# rPiMIDIShield.net
KiCad netlist of a schematic drawn in EAGLE
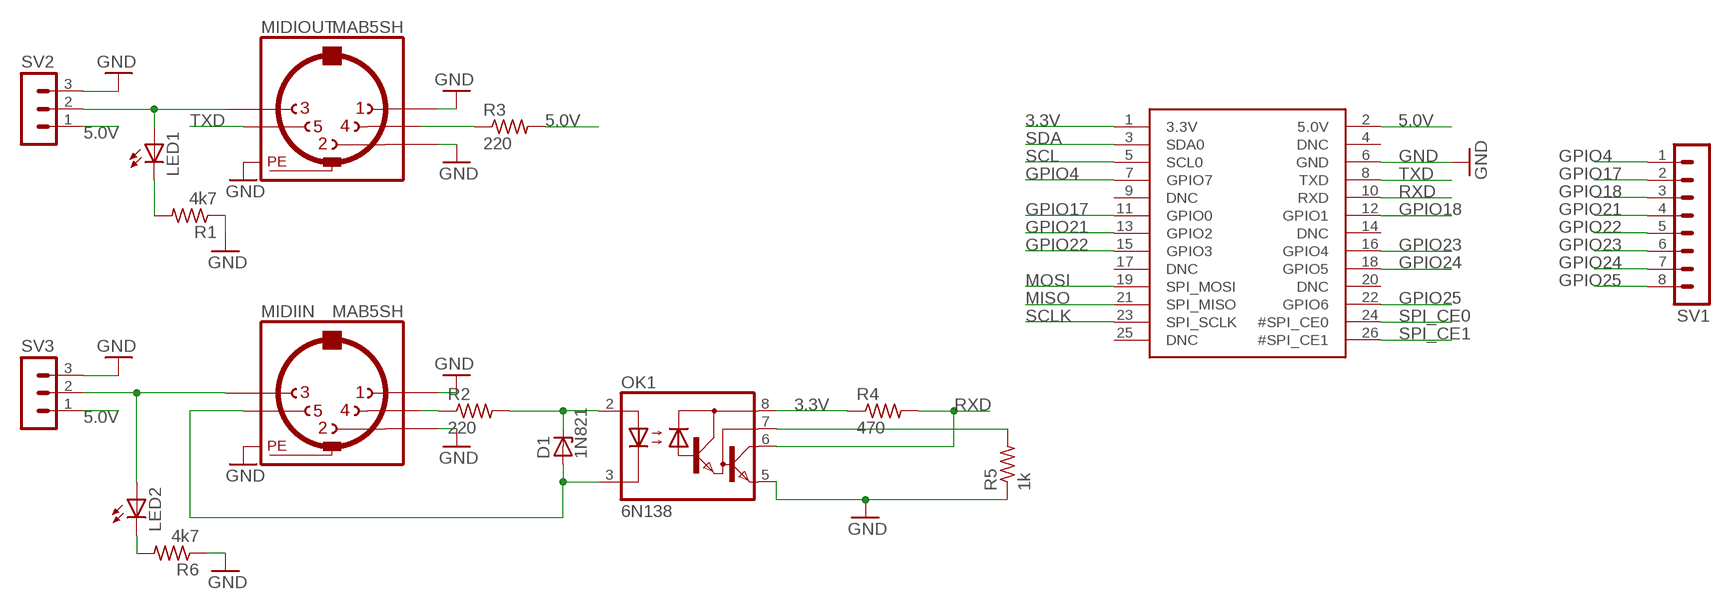
[diagram p0: schematic, sheet 1]

(export (version "E")
  (design (tool "Eeschema 10.0.6"))
  (components
    (comp (ref "D1")
      (value "1N821")
      (footprint "eagle-import:DO35Z10")
      (libsource (lib "eagle-import") (part "1N821"))
    )
    (comp (ref "GPIO")
      (value "RASPBERRYPI_BB")
      (footprint "eagle-import:RASBERRYPI_SHIELD")
      (libsource (lib "eagle-import") (part "RASPBERRYPI_BB"))
    )
    (comp (ref "LED1")
      (value "LEDLSU260")
      (footprint "eagle-import:LSU260")
      (libsource (lib "eagle-import") (part "LEDLSU260"))
    )
    (comp (ref "LED2")
      (value "LEDLSU260")
      (footprint "eagle-import:LSU260")
      (libsource (lib "eagle-import") (part "LEDLSU260"))
    )
    (comp (ref "MIDIIN")
      (value "MAB5SH")
      (footprint "eagle-import:MAB5SH")
      (libsource (lib "eagle-import") (part "MAB5SH"))
    )
    (comp (ref "MIDIOUT")
      (value "MAB5SH")
      (footprint "eagle-import:MAB5SH")
      (libsource (lib "eagle-import") (part "MAB5SH"))
    )
    (comp (ref "OK1")
      (value "6N138")
      (footprint "eagle-import:DIL08")
      (fields (field (name "MF") "VISHAY/TELEFUNKEN"))
      (libsource (lib "eagle-import") (part "6N138"))
    )
    (comp (ref "R1")
      (value "4k7")
      (footprint "eagle-import:0204_7")
      (libsource (lib "eagle-import") (part "R-US_0204/7"))
    )
    (comp (ref "R2")
      (value "220")
      (footprint "eagle-import:0204_7")
      (libsource (lib "eagle-import") (part "R-US_0204/7"))
    )
    (comp (ref "R3")
      (value "220")
      (footprint "eagle-import:0204_7")
      (libsource (lib "eagle-import") (part "R-US_0204/7"))
    )
    (comp (ref "R4")
      (value "470")
      (footprint "eagle-import:0204_7")
      (libsource (lib "eagle-import") (part "R-US_0204/7"))
    )
    (comp (ref "R5")
      (value "1k")
      (footprint "eagle-import:0204_7")
      (libsource (lib "eagle-import") (part "R-US_0204/7"))
    )
    (comp (ref "R6")
      (value "4k7")
      (footprint "eagle-import:0204_7")
      (libsource (lib "eagle-import") (part "R-US_0204/7"))
    )
    (comp (ref "SV1")
      (value "MA08-1")
      (footprint "eagle-import:MA08-1")
      (libsource (lib "eagle-import") (part "MA08-1"))
    )
    (comp (ref "SV2")
      (value "MA03-1")
      (footprint "eagle-import:MA03-1")
      (libsource (lib "eagle-import") (part "MA03-1"))
    )
    (comp (ref "SV3")
      (value "MA03-1")
      (footprint "eagle-import:MA03-1")
      (libsource (lib "eagle-import") (part "MA03-1"))
    )
  )
  (nets
    (net (code "1") (name "/3.3V") (class "Default")
      (node (ref "GPIO") (pin "1") (pinfunction "3.3V_1") (pintype "power_in"))
      (node (ref "OK1") (pin "8") (pinfunction "VCC_8") (pintype "passive"))
      (node (ref "R4") (pin "1") (pinfunction "1_1") (pintype "passive"))
    )
    (net (code "2") (name "/5.0V") (class "Default")
      (node (ref "GPIO") (pin "2") (pinfunction "5.0V_2") (pintype "power_in"))
      (node (ref "R3") (pin "2") (pinfunction "2_2") (pintype "passive"))
      (node (ref "SV2") (pin "1") (pinfunction "1_1") (pintype "passive"))
      (node (ref "SV3") (pin "1") (pinfunction "1_1") (pintype "passive"))
    )
    (net (code "3") (name "/GPIO4") (class "Default")
      (node (ref "GPIO") (pin "7") (pinfunction "GPIO7_7") (pintype "bidirectional"))
      (node (ref "SV1") (pin "1") (pinfunction "1_1") (pintype "passive"))
    )
    (net (code "4") (name "/GPIO17") (class "Default")
      (node (ref "GPIO") (pin "11") (pinfunction "GPIO0_11") (pintype "bidirectional"))
      (node (ref "SV1") (pin "2") (pinfunction "2_2") (pintype "passive"))
    )
    (net (code "5") (name "/GPIO18") (class "Default")
      (node (ref "GPIO") (pin "12") (pinfunction "GPIO1_12") (pintype "bidirectional"))
      (node (ref "SV1") (pin "3") (pinfunction "3_3") (pintype "passive"))
    )
    (net (code "6") (name "/GPIO21") (class "Default")
      (node (ref "GPIO") (pin "13") (pinfunction "GPIO2_13") (pintype "bidirectional"))
      (node (ref "SV1") (pin "4") (pinfunction "4_4") (pintype "passive"))
    )
    (net (code "7") (name "/GPIO22") (class "Default")
      (node (ref "GPIO") (pin "15") (pinfunction "GPIO3_15") (pintype "bidirectional"))
      (node (ref "SV1") (pin "5") (pinfunction "5_5") (pintype "passive"))
    )
    (net (code "8") (name "/GPIO23") (class "Default")
      (node (ref "GPIO") (pin "16") (pinfunction "GPIO4_16") (pintype "bidirectional"))
      (node (ref "SV1") (pin "6") (pinfunction "6_6") (pintype "passive"))
    )
    (net (code "9") (name "/GPIO24") (class "Default")
      (node (ref "GPIO") (pin "18") (pinfunction "GPIO5_18") (pintype "bidirectional"))
      (node (ref "SV1") (pin "7") (pinfunction "7_7") (pintype "passive"))
    )
    (net (code "10") (name "/GPIO25") (class "Default")
      (node (ref "GPIO") (pin "22") (pinfunction "GPIO6_22") (pintype "bidirectional"))
      (node (ref "SV1") (pin "8") (pinfunction "8_8") (pintype "passive"))
    )
    (net (code "11") (name "/MISO") (class "Default")
      (node (ref "GPIO") (pin "21") (pinfunction "SPI_MISO_21") (pintype "input"))
    )
    (net (code "12") (name "/MOSI") (class "Default")
      (node (ref "GPIO") (pin "19") (pinfunction "SPI_MOSI_19") (pintype "output"))
    )
    (net (code "13") (name "/RXD") (class "Default")
      (node (ref "GPIO") (pin "10") (pinfunction "RXD_10") (pintype "input"))
      (node (ref "OK1") (pin "6") (pinfunction "VO_6") (pintype "passive"))
      (node (ref "R4") (pin "2") (pinfunction "2_2") (pintype "passive"))
    )
    (net (code "14") (name "/SCL") (class "Default")
      (node (ref "GPIO") (pin "5") (pinfunction "SCL0_5") (pintype "output"))
    )
    (net (code "15") (name "/SCLK") (class "Default")
      (node (ref "GPIO") (pin "23") (pinfunction "SPI_SCLK_23") (pintype "output"))
    )
    (net (code "16") (name "/SDA") (class "Default")
      (node (ref "GPIO") (pin "3") (pinfunction "SDA0_3") (pintype "bidirectional"))
    )
    (net (code "17") (name "/SPI_CE0") (class "Default")
      (node (ref "GPIO") (pin "24") (pinfunction "#SPI_CE0_24") (pintype "output"))
    )
    (net (code "18") (name "/SPI_CE1") (class "Default")
      (node (ref "GPIO") (pin "26") (pinfunction "#SPI_CE1_26") (pintype "output"))
    )
    (net (code "19") (name "/TXD") (class "Default")
      (node (ref "GPIO") (pin "8") (pinfunction "TXD_8") (pintype "output"))
      (node (ref "MIDIOUT") (pin "5") (pinfunction "5_5") (pintype "passive"))
    )
    (net (code "20") (name "GND") (class "Default")
      (node (ref "GPIO") (pin "6") (pinfunction "GND_6") (pintype "power_in"))
      (node (ref "MIDIIN") (pin "1") (pinfunction "1_1") (pintype "passive"))
      (node (ref "MIDIIN") (pin "2") (pinfunction "2_2") (pintype "passive"))
      (node (ref "MIDIIN") (pin "PE") (pinfunction "PE_PE") (pintype "power_in"))
      (node (ref "MIDIIN") (pin "PE@") (pinfunction "PE_PE@") (pintype "power_in"))
      (node (ref "MIDIOUT") (pin "1") (pinfunction "1_1") (pintype "passive"))
      (node (ref "MIDIOUT") (pin "2") (pinfunction "2_2") (pintype "passive"))
      (node (ref "MIDIOUT") (pin "PE") (pinfunction "PE_PE") (pintype "power_in"))
      (node (ref "MIDIOUT") (pin "PE@") (pinfunction "PE_PE@") (pintype "power_in"))
      (node (ref "OK1") (pin "5") (pinfunction "GND_5") (pintype "passive"))
      (node (ref "R1") (pin "1") (pinfunction "1_1") (pintype "passive"))
      (node (ref "R5") (pin "1") (pinfunction "1_1") (pintype "passive"))
      (node (ref "R6") (pin "1") (pinfunction "1_1") (pintype "passive"))
      (node (ref "SV2") (pin "3") (pinfunction "3_3") (pintype "passive"))
      (node (ref "SV3") (pin "3") (pinfunction "3_3") (pintype "passive"))
    )
    (net (code "21") (name "Net-(LED1-C)") (class "Default")
      (node (ref "LED1") (pin "K") (pinfunction "C_K") (pintype "passive"))
      (node (ref "R1") (pin "2") (pinfunction "2_2") (pintype "passive"))
    )
    (net (code "22") (name "Net-(LED1-PadA)") (class "Default")
      (node (ref "LED1") (pin "A") (pinfunction "A_A") (pintype "passive"))
      (node (ref "MIDIOUT") (pin "3") (pinfunction "3_3") (pintype "passive"))
      (node (ref "SV2") (pin "2") (pinfunction "2_2") (pintype "passive"))
    )
    (net (code "23") (name "Net-(LED2-C)") (class "Default")
      (node (ref "LED2") (pin "K") (pinfunction "C_K") (pintype "passive"))
      (node (ref "R6") (pin "2") (pinfunction "2_2") (pintype "passive"))
    )
    (net (code "24") (name "Net-(LED2-PadA)") (class "Default")
      (node (ref "LED2") (pin "A") (pinfunction "A_A") (pintype "passive"))
      (node (ref "MIDIIN") (pin "3") (pinfunction "3_3") (pintype "passive"))
      (node (ref "SV3") (pin "2") (pinfunction "2_2") (pintype "passive"))
    )
    (net (code "25") (name "Net-(MIDIIN-Pad4)") (class "Default")
      (node (ref "MIDIIN") (pin "4") (pinfunction "4_4") (pintype "passive"))
      (node (ref "R2") (pin "1") (pinfunction "1_1") (pintype "passive"))
    )
    (net (code "26") (name "Net-(MIDIOUT-Pad4)") (class "Default")
      (node (ref "MIDIOUT") (pin "4") (pinfunction "4_4") (pintype "passive"))
      (node (ref "R3") (pin "1") (pinfunction "1_1") (pintype "passive"))
    )
    (net (code "27") (name "Net-(OK1-A)") (class "Default")
      (node (ref "D1") (pin "C") (pinfunction "C_C") (pintype "passive"))
      (node (ref "OK1") (pin "2") (pinfunction "A_2") (pintype "passive"))
      (node (ref "R2") (pin "2") (pinfunction "2_2") (pintype "passive"))
    )
    (net (code "28") (name "Net-(OK1-C)") (class "Default")
      (node (ref "D1") (pin "A") (pinfunction "A_A") (pintype "passive"))
      (node (ref "MIDIIN") (pin "5") (pinfunction "5_5") (pintype "passive"))
      (node (ref "OK1") (pin "3") (pinfunction "C_3") (pintype "passive"))
    )
    (net (code "29") (name "Net-(OK1-VB)") (class "Default")
      (node (ref "OK1") (pin "7") (pinfunction "VB_7") (pintype "passive"))
      (node (ref "R5") (pin "2") (pinfunction "2_2") (pintype "passive"))
    )
    (net (code "30") (name "unconnected-(GPIO-DNC-Pad4)") (class "Default")
      (node (ref "GPIO") (pin "4") (pinfunction "DNC_4") (pintype "no_connect"))
    )
    (net (code "31") (name "unconnected-(GPIO-DNC-Pad9)") (class "Default")
      (node (ref "GPIO") (pin "9") (pinfunction "DNC_9") (pintype "no_connect"))
    )
    (net (code "32") (name "unconnected-(GPIO-DNC-Pad14)") (class "Default")
      (node (ref "GPIO") (pin "14") (pinfunction "DNC_14") (pintype "no_connect"))
    )
    (net (code "33") (name "unconnected-(GPIO-DNC-Pad17)") (class "Default")
      (node (ref "GPIO") (pin "17") (pinfunction "DNC_17") (pintype "no_connect"))
    )
    (net (code "34") (name "unconnected-(GPIO-DNC-Pad20)") (class "Default")
      (node (ref "GPIO") (pin "20") (pinfunction "DNC_20") (pintype "no_connect"))
    )
    (net (code "35") (name "unconnected-(GPIO-DNC-Pad25)") (class "Default")
      (node (ref "GPIO") (pin "25") (pinfunction "DNC_25") (pintype "no_connect"))
    )
  )
)
